# 5_8.net
KiCad netlist of a schematic drawn in Altium Designer
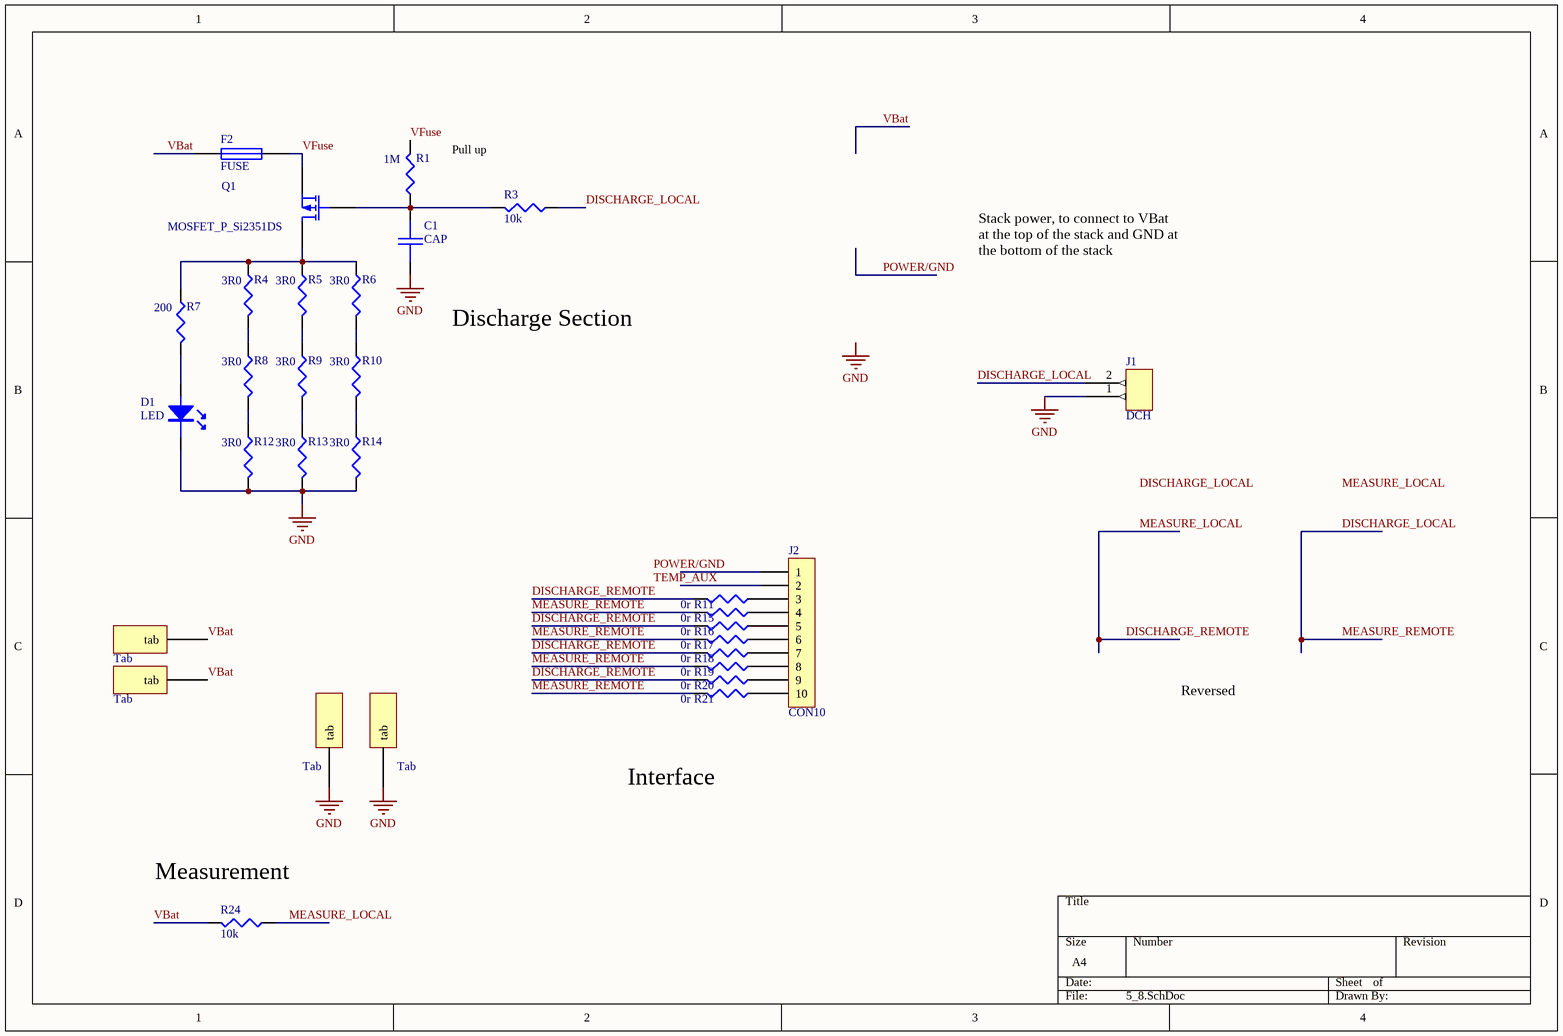
[diagram p0: 5_8.SchDoc]

(export (version "E")
  (design (tool "Eeschema 10.0.6"))
  (components
    (comp (ref "C1")
      (value "CAP")
      (footprint "0603")
      (description "Capacitor")
      (libsource (lib "RCLDQ") (part "CAP"))
    )
    (comp (ref "D1") (value "LED") (footprint "0805LED") (libsource (lib "RCLDQ") (part "LED")))
    (comp (ref "F2")
      (value "FUSE")
      (footprint "LITTELFUSE-154")
      (description "Fuse")
      (libsource (lib "Miscellaneous") (part "FUSE"))
    )
    (comp (ref "J1") (value "DCH") (footprint "IDC2") (libsource (lib "Connectors") (part "CON2")))
    (comp (ref "J2")
      (value "CON10")
      (footprint "IDC10")
      (description "10 pin, right angle, ribbon con with claws")
      (libsource (lib "Connectors") (part "CON10"))
    )
    (comp (ref "J4") (value "Tab") (footprint "tab_connect") (libsource (lib "") (part "tab_connection_1")))
    (comp (ref "J5") (value "Tab") (footprint "tab_connect") (libsource (lib "") (part "tab_connection_1")))
    (comp (ref "J6") (value "Tab") (footprint "tab_connect") (libsource (lib "BMS") (part "tab_connection")))
    (comp (ref "J7") (value "Tab") (footprint "tab_connect") (libsource (lib "BMS") (part "tab_connection")))
    (comp (ref "Q1")
      (value "MOSFET_P_Si2351DS")
      (footprint "SOT23-3")
      (description "Si2351DS P-Channel MOSFET")
      (fields (field (name "PUBLISHER") "Altium Limited"))
      (libsource (lib "RCLDQ") (part "MOSFET_P_Si2351DS"))
    )
    (comp (ref "R1")
      (value "~")
      (footprint "0603")
      (description "Resistor")
      (fields (field (name "RESISTANCE") "1M"))
      (libsource (lib "RCLDQ") (part "RES1"))
    )
    (comp (ref "R3")
      (value "~")
      (footprint "0603")
      (description "Resistor")
      (fields (field (name "RESISTANCE") "10k"))
      (libsource (lib "RCLDQ") (part "RES1"))
    )
    (comp (ref "R4")
      (value "3R0")
      (footprint "2512")
      (description "Resistor")
      (libsource (lib "RCLDQ") (part "RES1"))
    )
    (comp (ref "R5")
      (value "3R0")
      (footprint "2512")
      (description "Resistor")
      (libsource (lib "RCLDQ") (part "RES1"))
    )
    (comp (ref "R6")
      (value "3R0")
      (footprint "2512")
      (description "Resistor")
      (libsource (lib "RCLDQ") (part "RES1"))
    )
    (comp (ref "R7")
      (value "200")
      (footprint "0603")
      (description "Resistor")
      (libsource (lib "RCLDQ") (part "RES1"))
    )
    (comp (ref "R8")
      (value "3R0")
      (footprint "2512")
      (description "Resistor")
      (libsource (lib "RCLDQ") (part "RES1"))
    )
    (comp (ref "R9")
      (value "3R0")
      (footprint "2512")
      (description "Resistor")
      (libsource (lib "RCLDQ") (part "RES1"))
    )
    (comp (ref "R10")
      (value "3R0")
      (footprint "2512")
      (description "Resistor")
      (libsource (lib "RCLDQ") (part "RES1"))
    )
    (comp (ref "R11")
      (value "~")
      (footprint "0603")
      (description "Resistor")
      (fields (field (name "RESISTANCE") "0r"))
      (libsource (lib "RCLDQ") (part "RES1"))
    )
    (comp (ref "R12")
      (value "3R0")
      (footprint "2512")
      (description "Resistor")
      (libsource (lib "RCLDQ") (part "RES1"))
    )
    (comp (ref "R13")
      (value "3R0")
      (footprint "2512")
      (description "Resistor")
      (libsource (lib "RCLDQ") (part "RES1"))
    )
    (comp (ref "R14")
      (value "3R0")
      (footprint "2512")
      (description "Resistor")
      (libsource (lib "RCLDQ") (part "RES1"))
    )
    (comp (ref "R15")
      (value "~")
      (footprint "0603")
      (description "Resistor")
      (fields (field (name "RESISTANCE") "0r"))
      (libsource (lib "RCLDQ") (part "RES1"))
    )
    (comp (ref "R16")
      (value "~")
      (footprint "0603")
      (description "Resistor")
      (fields (field (name "RESISTANCE") "0r"))
      (libsource (lib "RCLDQ") (part "RES1"))
    )
    (comp (ref "R17")
      (value "~")
      (footprint "0603")
      (description "Resistor")
      (fields (field (name "RESISTANCE") "0r"))
      (libsource (lib "RCLDQ") (part "RES1"))
    )
    (comp (ref "R18")
      (value "~")
      (footprint "0603")
      (description "Resistor")
      (fields (field (name "RESISTANCE") "0r"))
      (libsource (lib "RCLDQ") (part "RES1"))
    )
    (comp (ref "R19")
      (value "~")
      (footprint "0603")
      (description "Resistor")
      (fields (field (name "RESISTANCE") "0r"))
      (libsource (lib "RCLDQ") (part "RES1"))
    )
    (comp (ref "R20")
      (value "~")
      (footprint "0603")
      (description "Resistor")
      (fields (field (name "RESISTANCE") "0r"))
      (libsource (lib "RCLDQ") (part "RES1"))
    )
    (comp (ref "R21")
      (value "~")
      (footprint "0603")
      (description "Resistor")
      (fields (field (name "RESISTANCE") "0r"))
      (libsource (lib "RCLDQ") (part "RES1"))
    )
    (comp (ref "R24")
      (value "~")
      (footprint "0603")
      (description "Resistor")
      (fields (field (name "RESISTANCE") "10k"))
      (libsource (lib "RCLDQ") (part "RES1"))
    )
  )
  (nets
    (net (code "1") (name "/DISCHARGE_LOCAL") (class "Default")
      (node (ref "J1") (pin "2") (pinfunction "2_2") (pintype "output"))
      (node (ref "R15") (pin "2") (pinfunction "2_2") (pintype "passive"))
      (node (ref "R17") (pin "2") (pinfunction "2_2") (pintype "passive"))
      (node (ref "R19") (pin "2") (pinfunction "2_2") (pintype "passive"))
      (node (ref "R21") (pin "2") (pinfunction "2_2") (pintype "passive"))
      (node (ref "R3") (pin "1") (pinfunction "1_1") (pintype "passive"))
    )
    (net (code "2") (name "/DISCHARGE_REMOTE") (class "Default")
      (node (ref "R11") (pin "2") (pinfunction "2_2") (pintype "passive"))
      (node (ref "R16") (pin "2") (pinfunction "2_2") (pintype "passive"))
      (node (ref "R18") (pin "2") (pinfunction "2_2") (pintype "passive"))
      (node (ref "R20") (pin "2") (pinfunction "2_2") (pintype "passive"))
      (node (ref "R24") (pin "1") (pinfunction "1_1") (pintype "passive"))
    )
    (net (code "5") (name "/VBat") (class "Default")
      (node (ref "F2") (pin "1") (pinfunction "1_1") (pintype "passive"))
      (node (ref "J4") (pin "0") (pinfunction "tab_0") (pintype "passive"))
      (node (ref "J5") (pin "0") (pinfunction "tab_0") (pintype "passive"))
      (node (ref "R24") (pin "2") (pinfunction "2_2") (pintype "passive"))
    )
    (net (code "6") (name "/VFuse") (class "Default")
      (node (ref "F2") (pin "2") (pinfunction "2_2") (pintype "passive"))
      (node (ref "Q1") (pin "2") (pinfunction "S_2") (pintype "passive"))
      (node (ref "R1") (pin "2") (pinfunction "2_2") (pintype "passive"))
    )
    (net (code "7") (name "GND") (class "Default")
      (node (ref "C1") (pin "2") (pinfunction "2_2") (pintype "passive"))
      (node (ref "D1") (pin "K") (pinfunction "K_K") (pintype "passive"))
      (node (ref "J1") (pin "1") (pinfunction "1_1") (pintype "output"))
      (node (ref "J6") (pin "0") (pinfunction "tab_0") (pintype "passive"))
      (node (ref "J7") (pin "0") (pinfunction "tab_0") (pintype "passive"))
      (node (ref "R12") (pin "2") (pinfunction "2_2") (pintype "passive"))
      (node (ref "R13") (pin "2") (pinfunction "2_2") (pintype "passive"))
      (node (ref "R14") (pin "2") (pinfunction "2_2") (pintype "passive"))
    )
    (net (code "8") (name "Net-(D1-PadA)") (class "Default")
      (node (ref "D1") (pin "A") (pinfunction "A_A") (pintype "passive"))
      (node (ref "R7") (pin "2") (pinfunction "2_2") (pintype "passive"))
    )
    (net (code "9") (name "Net-(J2-Pad3)") (class "Default")
      (node (ref "J2") (pin "3") (pinfunction "3_3") (pintype "passive"))
      (node (ref "R11") (pin "1") (pinfunction "1_1") (pintype "passive"))
    )
    (net (code "10") (name "Net-(J2-Pad4)") (class "Default")
      (node (ref "J2") (pin "4") (pinfunction "4_4") (pintype "passive"))
      (node (ref "R15") (pin "1") (pinfunction "1_1") (pintype "passive"))
    )
    (net (code "11") (name "Net-(J2-Pad5)") (class "Default")
      (node (ref "J2") (pin "5") (pinfunction "5_5") (pintype "passive"))
      (node (ref "R16") (pin "1") (pinfunction "1_1") (pintype "passive"))
    )
    (net (code "12") (name "Net-(J2-Pad6)") (class "Default")
      (node (ref "J2") (pin "6") (pinfunction "6_6") (pintype "passive"))
      (node (ref "R17") (pin "1") (pinfunction "1_1") (pintype "passive"))
    )
    (net (code "13") (name "Net-(J2-Pad7)") (class "Default")
      (node (ref "J2") (pin "7") (pinfunction "7_7") (pintype "passive"))
      (node (ref "R18") (pin "1") (pinfunction "1_1") (pintype "passive"))
    )
    (net (code "14") (name "Net-(J2-Pad8)") (class "Default")
      (node (ref "J2") (pin "8") (pinfunction "8_8") (pintype "passive"))
      (node (ref "R19") (pin "1") (pinfunction "1_1") (pintype "passive"))
    )
    (net (code "15") (name "Net-(J2-Pad9)") (class "Default")
      (node (ref "J2") (pin "9") (pinfunction "9_9") (pintype "passive"))
      (node (ref "R20") (pin "1") (pinfunction "1_1") (pintype "passive"))
    )
    (net (code "16") (name "Net-(J2-Pad10)") (class "Default")
      (node (ref "J2") (pin "10") (pinfunction "10_10") (pintype "passive"))
      (node (ref "R21") (pin "1") (pinfunction "1_1") (pintype "passive"))
    )
    (net (code "17") (name "Net-(Q1-D)") (class "Default")
      (node (ref "Q1") (pin "3") (pinfunction "D_3") (pintype "passive"))
      (node (ref "R4") (pin "1") (pinfunction "1_1") (pintype "passive"))
      (node (ref "R5") (pin "1") (pinfunction "1_1") (pintype "passive"))
      (node (ref "R6") (pin "1") (pinfunction "1_1") (pintype "passive"))
      (node (ref "R7") (pin "1") (pinfunction "1_1") (pintype "passive"))
    )
    (net (code "18") (name "Net-(Q1-G)") (class "Default")
      (node (ref "C1") (pin "1") (pinfunction "1_1") (pintype "passive"))
      (node (ref "Q1") (pin "1") (pinfunction "G_1") (pintype "passive"))
      (node (ref "R1") (pin "1") (pinfunction "1_1") (pintype "passive"))
      (node (ref "R3") (pin "2") (pinfunction "2_2") (pintype "passive"))
    )
    (net (code "19") (name "Net-(R4-Pad2)") (class "Default")
      (node (ref "R4") (pin "2") (pinfunction "2_2") (pintype "passive"))
      (node (ref "R8") (pin "1") (pinfunction "1_1") (pintype "passive"))
    )
    (net (code "20") (name "Net-(R5-Pad2)") (class "Default")
      (node (ref "R5") (pin "2") (pinfunction "2_2") (pintype "passive"))
      (node (ref "R9") (pin "1") (pinfunction "1_1") (pintype "passive"))
    )
    (net (code "21") (name "Net-(R10-Pad1)") (class "Default")
      (node (ref "R10") (pin "1") (pinfunction "1_1") (pintype "passive"))
      (node (ref "R6") (pin "2") (pinfunction "2_2") (pintype "passive"))
    )
    (net (code "22") (name "Net-(R10-Pad2)") (class "Default")
      (node (ref "R10") (pin "2") (pinfunction "2_2") (pintype "passive"))
      (node (ref "R14") (pin "1") (pinfunction "1_1") (pintype "passive"))
    )
    (net (code "23") (name "Net-(R12-Pad1)") (class "Default")
      (node (ref "R12") (pin "1") (pinfunction "1_1") (pintype "passive"))
      (node (ref "R8") (pin "2") (pinfunction "2_2") (pintype "passive"))
    )
    (net (code "24") (name "Net-(R13-Pad1)") (class "Default")
      (node (ref "R13") (pin "1") (pinfunction "1_1") (pintype "passive"))
      (node (ref "R9") (pin "2") (pinfunction "2_2") (pintype "passive"))
    )
    (net (code "25") (name "unconnected-(J2-Pad1)") (class "Default")
      (node (ref "J2") (pin "1") (pinfunction "1_1") (pintype "passive"))
    )
    (net (code "26") (name "unconnected-(J2-Pad2)") (class "Default")
      (node (ref "J2") (pin "2") (pinfunction "2_2") (pintype "passive"))
    )
  )
)
